# Prototype.net
KiCad netlist of a schematic drawn in EAGLE
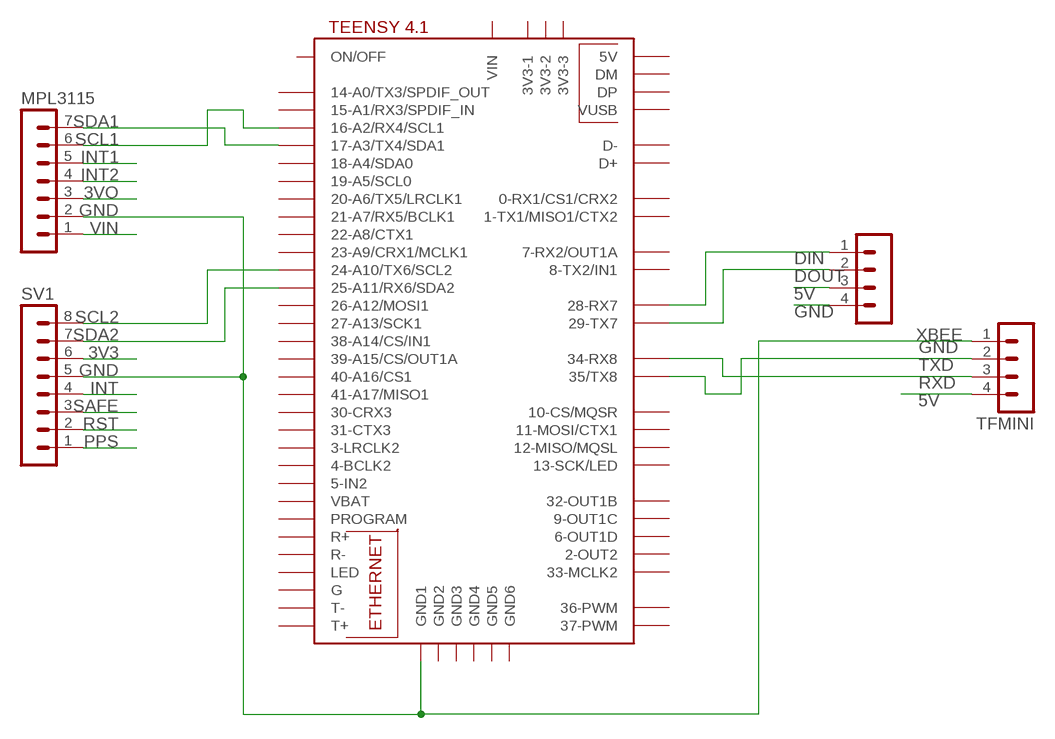
[diagram p0: schematic, sheet 1]

(export (version "E")
  (design (tool "Eeschema 10.0.6"))
  (components
    (comp (ref "MPL3115")
      (value "MA07-1")
      (footprint "eagle-import:MA07-1")
      (libsource (lib "eagle-import") (part "MA07-1"))
    )
    (comp (ref "SV1")
      (value "MA08-1")
      (footprint "eagle-import:MA08-1")
      (libsource (lib "eagle-import") (part "MA08-1"))
    )
    (comp (ref "TFMINI")
      (value "MA04-1")
      (footprint "eagle-import:MA04-1")
      (libsource (lib "eagle-import") (part "MA04-1"))
    )
    (comp (ref "U$1")
      (value "TEENSY41")
      (footprint "eagle-import:TEENSY41")
      (libsource (lib "eagle-import") (part "TEENSY41"))
    )
    (comp (ref "XBEE")
      (value "MA04-1")
      (footprint "eagle-import:MA04-1")
      (libsource (lib "eagle-import") (part "MA04-1"))
    )
  )
  (nets
    (net (code "1") (name "/3V3") (class "Default")
      (node (ref "SV1") (pin "6") (pinfunction "6_6") (pintype "passive"))
    )
    (net (code "2") (name "/3VO") (class "Default")
      (node (ref "MPL3115") (pin "3") (pinfunction "3_3") (pintype "passive"))
    )
    (net (code "3") (name "/5V") (class "Default")
      (node (ref "TFMINI") (pin "4") (pinfunction "4_4") (pintype "passive"))
      (node (ref "XBEE") (pin "3") (pinfunction "3_3") (pintype "passive"))
    )
    (net (code "4") (name "/DIN") (class "Default")
      (node (ref "U$1") (pin "28-RX7") (pinfunction "28-RX7_28-RX7") (pintype "bidirectional"))
      (node (ref "XBEE") (pin "1") (pinfunction "1_1") (pintype "passive"))
    )
    (net (code "5") (name "/DOUT") (class "Default")
      (node (ref "U$1") (pin "29-TX7") (pinfunction "29-TX7_29-TX7") (pintype "bidirectional"))
      (node (ref "XBEE") (pin "2") (pinfunction "2_2") (pintype "passive"))
    )
    (net (code "6") (name "/GND") (class "Default")
      (node (ref "MPL3115") (pin "2") (pinfunction "2_2") (pintype "passive"))
      (node (ref "SV1") (pin "5") (pinfunction "5_5") (pintype "passive"))
      (node (ref "TFMINI") (pin "1") (pinfunction "1_1") (pintype "passive"))
      (node (ref "U$1") (pin "GND1") (pinfunction "GND1_GND1") (pintype "bidirectional"))
      (node (ref "XBEE") (pin "4") (pinfunction "4_4") (pintype "passive"))
    )
    (net (code "7") (name "/INT") (class "Default")
      (node (ref "SV1") (pin "4") (pinfunction "4_4") (pintype "passive"))
    )
    (net (code "8") (name "/INT1") (class "Default")
      (node (ref "MPL3115") (pin "5") (pinfunction "5_5") (pintype "passive"))
    )
    (net (code "9") (name "/INT2") (class "Default")
      (node (ref "MPL3115") (pin "4") (pinfunction "4_4") (pintype "passive"))
    )
    (net (code "10") (name "/PPS") (class "Default")
      (node (ref "SV1") (pin "1") (pinfunction "1_1") (pintype "passive"))
    )
    (net (code "11") (name "/RST") (class "Default")
      (node (ref "SV1") (pin "2") (pinfunction "2_2") (pintype "passive"))
    )
    (net (code "12") (name "/RXD") (class "Default")
      (node (ref "TFMINI") (pin "3") (pinfunction "3_3") (pintype "passive"))
      (node (ref "U$1") (pin "34-RX8") (pinfunction "34-RX8_34-RX8") (pintype "bidirectional"))
    )
    (net (code "13") (name "/SAFE") (class "Default")
      (node (ref "SV1") (pin "3") (pinfunction "3_3") (pintype "passive"))
    )
    (net (code "14") (name "/SCL1") (class "Default")
      (node (ref "MPL3115") (pin "6") (pinfunction "6_6") (pintype "passive"))
      (node (ref "U$1") (pin "16-A2/RX4/SCL1") (pinfunction "16-A2/RX4/SCL1_16-A2/RX4/SCL1") (pintype "bidirectional"))
    )
    (net (code "15") (name "/SCL2") (class "Default")
      (node (ref "SV1") (pin "8") (pinfunction "8_8") (pintype "passive"))
      (node (ref "U$1") (pin "24-A10/TX6/SCL2") (pinfunction "24-A10/TX6/SCL2_24-A10/TX6/SCL2") (pintype "bidirectional"))
    )
    (net (code "16") (name "/SDA1") (class "Default")
      (node (ref "MPL3115") (pin "7") (pinfunction "7_7") (pintype "passive"))
      (node (ref "U$1") (pin "17-A3/TX4/SDA1") (pinfunction "17-A3/TX4/SDA1_17-A3/TX4/SDA1") (pintype "bidirectional"))
    )
    (net (code "17") (name "/SDA2") (class "Default")
      (node (ref "SV1") (pin "7") (pinfunction "7_7") (pintype "passive"))
      (node (ref "U$1") (pin "25-A11/RX6/SDA2") (pinfunction "25-A11/RX6/SDA2_25-A11/RX6/SDA2") (pintype "bidirectional"))
    )
    (net (code "18") (name "/TXD") (class "Default")
      (node (ref "TFMINI") (pin "2") (pinfunction "2_2") (pintype "passive"))
      (node (ref "U$1") (pin "35-TX8") (pinfunction "35/TX8_35-TX8") (pintype "bidirectional"))
    )
    (net (code "19") (name "/VIN") (class "Default")
      (node (ref "MPL3115") (pin "1") (pinfunction "1_1") (pintype "passive"))
    )
    (net (code "20") (name "unconnected-(U$1-5V-Pad+5V)") (class "Default")
      (node (ref "U$1") (pin "+5V") (pinfunction "5V_+5V") (pintype "bidirectional"))
    )
    (net (code "21") (name "unconnected-(U$1-10-CS{slash}MQSR-Pad10-CS\\MQSR)") (class "Default")
      (node (ref "U$1") (pin "10-CS\\MQSR") (pinfunction "10-CS/MQSR_10-CS\\MQSR") (pintype "bidirectional"))
    )
    (net (code "22") (name "unconnected-(U$1-Pad0-RX1{slash}CS1{slash}CRX2)") (class "Default")
      (node (ref "U$1") (pin "0-RX1/CS1/CRX2") (pinfunction "0-RX1/CS1/CRX2_0-RX1/CS1/CRX2") (pintype "bidirectional"))
    )
    (net (code "23") (name "unconnected-(U$1-Pad1-TX1{slash}MISO1{slash}CTX2)") (class "Default")
      (node (ref "U$1") (pin "1-TX1/MISO1/CTX2") (pinfunction "1-TX1/MISO1/CTX2_1-TX1/MISO1/CTX2") (pintype "bidirectional"))
    )
    (net (code "24") (name "unconnected-(U$1-Pad2-OUT2)") (class "Default")
      (node (ref "U$1") (pin "2-OUT2") (pinfunction "2-OUT2_2-OUT2") (pintype "bidirectional"))
    )
    (net (code "25") (name "unconnected-(U$1-Pad3-LRCLK2)") (class "Default")
      (node (ref "U$1") (pin "3-LRCLK2") (pinfunction "3-LRCLK2_3-LRCLK2") (pintype "bidirectional"))
    )
    (net (code "26") (name "unconnected-(U$1-Pad3V3-1)") (class "Default")
      (node (ref "U$1") (pin "3V3-1") (pinfunction "3V3-1_3V3-1") (pintype "bidirectional"))
    )
    (net (code "27") (name "unconnected-(U$1-Pad3V3-2)") (class "Default")
      (node (ref "U$1") (pin "3V3-2") (pinfunction "3V3-2_3V3-2") (pintype "bidirectional"))
    )
    (net (code "28") (name "unconnected-(U$1-Pad3V3-3)") (class "Default")
      (node (ref "U$1") (pin "3V3-3") (pinfunction "3V3-3_3V3-3") (pintype "bidirectional"))
    )
    (net (code "29") (name "unconnected-(U$1-Pad4-BCLK2)") (class "Default")
      (node (ref "U$1") (pin "4-BCLK2") (pinfunction "4-BCLK2_4-BCLK2") (pintype "bidirectional"))
    )
    (net (code "30") (name "unconnected-(U$1-Pad5-IN2)") (class "Default")
      (node (ref "U$1") (pin "5-IN2") (pinfunction "5-IN2_5-IN2") (pintype "bidirectional"))
    )
    (net (code "31") (name "unconnected-(U$1-Pad6-OUT1D)") (class "Default")
      (node (ref "U$1") (pin "6-OUT1D") (pinfunction "6-OUT1D_6-OUT1D") (pintype "bidirectional"))
    )
    (net (code "32") (name "unconnected-(U$1-Pad7-RX2{slash}OUT1A)") (class "Default")
      (node (ref "U$1") (pin "7-RX2/OUT1A") (pinfunction "7-RX2/OUT1A_7-RX2/OUT1A") (pintype "bidirectional"))
    )
    (net (code "33") (name "unconnected-(U$1-Pad8-TX2{slash}IN1)") (class "Default")
      (node (ref "U$1") (pin "8-TX2/IN1") (pinfunction "8-TX2/IN1_8-TX2/IN1") (pintype "bidirectional"))
    )
    (net (code "34") (name "unconnected-(U$1-Pad9-OUT1C)") (class "Default")
      (node (ref "U$1") (pin "9-OUT1C") (pinfunction "9-OUT1C_9-OUT1C") (pintype "bidirectional"))
    )
    (net (code "35") (name "unconnected-(U$1-Pad11-MOSI{slash}CTX1)") (class "Default")
      (node (ref "U$1") (pin "11-MOSI/CTX1") (pinfunction "11-MOSI/CTX1_11-MOSI/CTX1") (pintype "bidirectional"))
    )
    (net (code "36") (name "unconnected-(U$1-Pad12-MISO{slash}MQSL)") (class "Default")
      (node (ref "U$1") (pin "12-MISO/MQSL") (pinfunction "12-MISO/MQSL_12-MISO/MQSL") (pintype "bidirectional"))
    )
    (net (code "37") (name "unconnected-(U$1-Pad13-SCK{slash}LED)") (class "Default")
      (node (ref "U$1") (pin "13-SCK/LED") (pinfunction "13-SCK/LED_13-SCK/LED") (pintype "bidirectional"))
    )
    (net (code "38") (name "unconnected-(U$1-Pad14-A0{slash}TX3{slash}SPDIF_OUT)") (class "Default")
      (node (ref "U$1") (pin "14-A0/TX3/SPDIF_OUT") (pinfunction "14-A0/TX3/SPDIF_OUT_14-A0/TX3/SPDIF_OUT") (pintype "bidirectional"))
    )
    (net (code "39") (name "unconnected-(U$1-Pad15-A1{slash}RX3{slash}SPDIF_IN)") (class "Default")
      (node (ref "U$1") (pin "15-A1/RX3/SPDIF_IN") (pinfunction "15-A1/RX3/SPDIF_IN_15-A1/RX3/SPDIF_IN") (pintype "bidirectional"))
    )
    (net (code "40") (name "unconnected-(U$1-Pad18-A4{slash}SDA0)") (class "Default")
      (node (ref "U$1") (pin "18-A4/SDA0") (pinfunction "18-A4/SDA0_18-A4/SDA0") (pintype "bidirectional"))
    )
    (net (code "41") (name "unconnected-(U$1-Pad19-A5{slash}SCL0)") (class "Default")
      (node (ref "U$1") (pin "19-A5/SCL0") (pinfunction "19-A5/SCL0_19-A5/SCL0") (pintype "bidirectional"))
    )
    (net (code "42") (name "unconnected-(U$1-Pad20-A6{slash}TX5{slash}LRCLK1)") (class "Default")
      (node (ref "U$1") (pin "20-A6/TX5/LRCLK1") (pinfunction "20-A6/TX5/LRCLK1_20-A6/TX5/LRCLK1") (pintype "bidirectional"))
    )
    (net (code "43") (name "unconnected-(U$1-Pad21-A7{slash}RX5{slash}BCLK1)") (class "Default")
      (node (ref "U$1") (pin "21-A7/RX5/BCLK1") (pinfunction "21-A7/RX5/BCLK1_21-A7/RX5/BCLK1") (pintype "bidirectional"))
    )
    (net (code "44") (name "unconnected-(U$1-Pad22-A8{slash}CTX1)") (class "Default")
      (node (ref "U$1") (pin "22-A8/CTX1") (pinfunction "22-A8/CTX1_22-A8/CTX1") (pintype "bidirectional"))
    )
    (net (code "45") (name "unconnected-(U$1-Pad23-A9{slash}CRX1{slash}MCLK1)") (class "Default")
      (node (ref "U$1") (pin "23-A9/CRX1/MCLK1") (pinfunction "23-A9/CRX1/MCLK1_23-A9/CRX1/MCLK1") (pintype "bidirectional"))
    )
    (net (code "46") (name "unconnected-(U$1-Pad26-A12{slash}MOSI1)") (class "Default")
      (node (ref "U$1") (pin "26-A12/MOSI1") (pinfunction "26-A12/MOSI1_26-A12/MOSI1") (pintype "bidirectional"))
    )
    (net (code "47") (name "unconnected-(U$1-Pad27-A13{slash}SCK1)") (class "Default")
      (node (ref "U$1") (pin "27-A13/SCK1") (pinfunction "27-A13/SCK1_27-A13/SCK1") (pintype "bidirectional"))
    )
    (net (code "48") (name "unconnected-(U$1-Pad30-CRX3)") (class "Default")
      (node (ref "U$1") (pin "30-CRX3") (pinfunction "30-CRX3_30-CRX3") (pintype "bidirectional"))
    )
    (net (code "49") (name "unconnected-(U$1-Pad31-CTX3)") (class "Default")
      (node (ref "U$1") (pin "31-CTX3") (pinfunction "31-CTX3_31-CTX3") (pintype "bidirectional"))
    )
    (net (code "50") (name "unconnected-(U$1-Pad32-OUT1B)") (class "Default")
      (node (ref "U$1") (pin "32-OUT1B") (pinfunction "32-OUT1B_32-OUT1B") (pintype "bidirectional"))
    )
    (net (code "51") (name "unconnected-(U$1-Pad33-MCLK2)") (class "Default")
      (node (ref "U$1") (pin "33-MCLK2") (pinfunction "33-MCLK2_33-MCLK2") (pintype "bidirectional"))
    )
    (net (code "52") (name "unconnected-(U$1-Pad36-PWM)") (class "Default")
      (node (ref "U$1") (pin "36-PWM") (pinfunction "36-PWM_36-PWM") (pintype "bidirectional"))
    )
    (net (code "53") (name "unconnected-(U$1-Pad37-PWM)") (class "Default")
      (node (ref "U$1") (pin "37-PWM") (pinfunction "37-PWM_37-PWM") (pintype "bidirectional"))
    )
    (net (code "54") (name "unconnected-(U$1-Pad38-A14{slash}CS{slash}IN1)") (class "Default")
      (node (ref "U$1") (pin "38-A14/CS/IN1") (pinfunction "38-A14/CS/IN1_38-A14/CS/IN1") (pintype "bidirectional"))
    )
    (net (code "55") (name "unconnected-(U$1-Pad39-A15{slash}CS{slash}OUT1A)") (class "Default")
      (node (ref "U$1") (pin "39-A15/CS/OUT1A") (pinfunction "39-A15/CS/OUT1A_39-A15/CS/OUT1A") (pintype "bidirectional"))
    )
    (net (code "56") (name "unconnected-(U$1-Pad40-A16{slash}CS1)") (class "Default")
      (node (ref "U$1") (pin "40-A16/CS1") (pinfunction "40-A16/CS1_40-A16/CS1") (pintype "bidirectional"))
    )
    (net (code "57") (name "unconnected-(U$1-Pad41-A17{slash}MISO1)") (class "Default")
      (node (ref "U$1") (pin "41-A17/MISO1") (pinfunction "41-A17/MISO1_41-A17/MISO1") (pintype "bidirectional"))
    )
    (net (code "58") (name "unconnected-(U$1-PadD+)") (class "Default")
      (node (ref "U$1") (pin "D+") (pinfunction "D+_D+") (pintype "bidirectional"))
    )
    (net (code "59") (name "unconnected-(U$1-PadD-)") (class "Default")
      (node (ref "U$1") (pin "D-") (pinfunction "D-_D-") (pintype "bidirectional"))
    )
    (net (code "60") (name "unconnected-(U$1-PadDM)") (class "Default")
      (node (ref "U$1") (pin "DM") (pinfunction "DM_DM") (pintype "bidirectional"))
    )
    (net (code "61") (name "unconnected-(U$1-PadDP)") (class "Default")
      (node (ref "U$1") (pin "DP") (pinfunction "DP_DP") (pintype "bidirectional"))
    )
    (net (code "62") (name "unconnected-(U$1-PadG)") (class "Default")
      (node (ref "U$1") (pin "G") (pinfunction "G_G") (pintype "bidirectional"))
    )
    (net (code "63") (name "unconnected-(U$1-PadGND2)") (class "Default")
      (node (ref "U$1") (pin "GND2") (pinfunction "GND2_GND2") (pintype "bidirectional"))
    )
    (net (code "64") (name "unconnected-(U$1-PadGND3)") (class "Default")
      (node (ref "U$1") (pin "GND3") (pinfunction "GND3_GND3") (pintype "bidirectional"))
    )
    (net (code "65") (name "unconnected-(U$1-PadGND4)") (class "Default")
      (node (ref "U$1") (pin "GND4") (pinfunction "GND4_GND4") (pintype "bidirectional"))
    )
    (net (code "66") (name "unconnected-(U$1-PadGND5)") (class "Default")
      (node (ref "U$1") (pin "GND5") (pinfunction "GND5_GND5") (pintype "bidirectional"))
    )
    (net (code "67") (name "unconnected-(U$1-PadGND6)") (class "Default")
      (node (ref "U$1") (pin "GND6") (pinfunction "GND6_GND6") (pintype "bidirectional"))
    )
    (net (code "68") (name "unconnected-(U$1-PadLED)") (class "Default")
      (node (ref "U$1") (pin "LED") (pinfunction "LED_LED") (pintype "bidirectional"))
    )
    (net (code "69") (name "unconnected-(U$1-PadON{slash}OFF)") (class "Default")
      (node (ref "U$1") (pin "ON/OFF") (pinfunction "ON/OFF_ON/OFF") (pintype "bidirectional"))
    )
    (net (code "70") (name "unconnected-(U$1-PadPROGRAM)") (class "Default")
      (node (ref "U$1") (pin "PROGRAM") (pinfunction "PROGRAM_PROGRAM") (pintype "bidirectional"))
    )
    (net (code "71") (name "unconnected-(U$1-PadR+)") (class "Default")
      (node (ref "U$1") (pin "R+") (pinfunction "R+_R+") (pintype "bidirectional"))
    )
    (net (code "72") (name "unconnected-(U$1-PadR-)") (class "Default")
      (node (ref "U$1") (pin "R-") (pinfunction "R-_R-") (pintype "bidirectional"))
    )
    (net (code "73") (name "unconnected-(U$1-PadT+)") (class "Default")
      (node (ref "U$1") (pin "T+") (pinfunction "T+_T+") (pintype "bidirectional"))
    )
    (net (code "74") (name "unconnected-(U$1-PadT-)") (class "Default")
      (node (ref "U$1") (pin "T-") (pinfunction "T-_T-") (pintype "bidirectional"))
    )
    (net (code "75") (name "unconnected-(U$1-PadVBAT)") (class "Default")
      (node (ref "U$1") (pin "VBAT") (pinfunction "VBAT_VBAT") (pintype "bidirectional"))
    )
    (net (code "76") (name "unconnected-(U$1-PadVIN)") (class "Default")
      (node (ref "U$1") (pin "VIN") (pinfunction "VIN_VIN") (pintype "bidirectional"))
    )
    (net (code "77") (name "unconnected-(U$1-PadVUSB)") (class "Default")
      (node (ref "U$1") (pin "VUSB") (pinfunction "VUSB_VUSB") (pintype "bidirectional"))
    )
  )
)
